# untitled.net
KiCad netlist of a schematic drawn in EAGLE
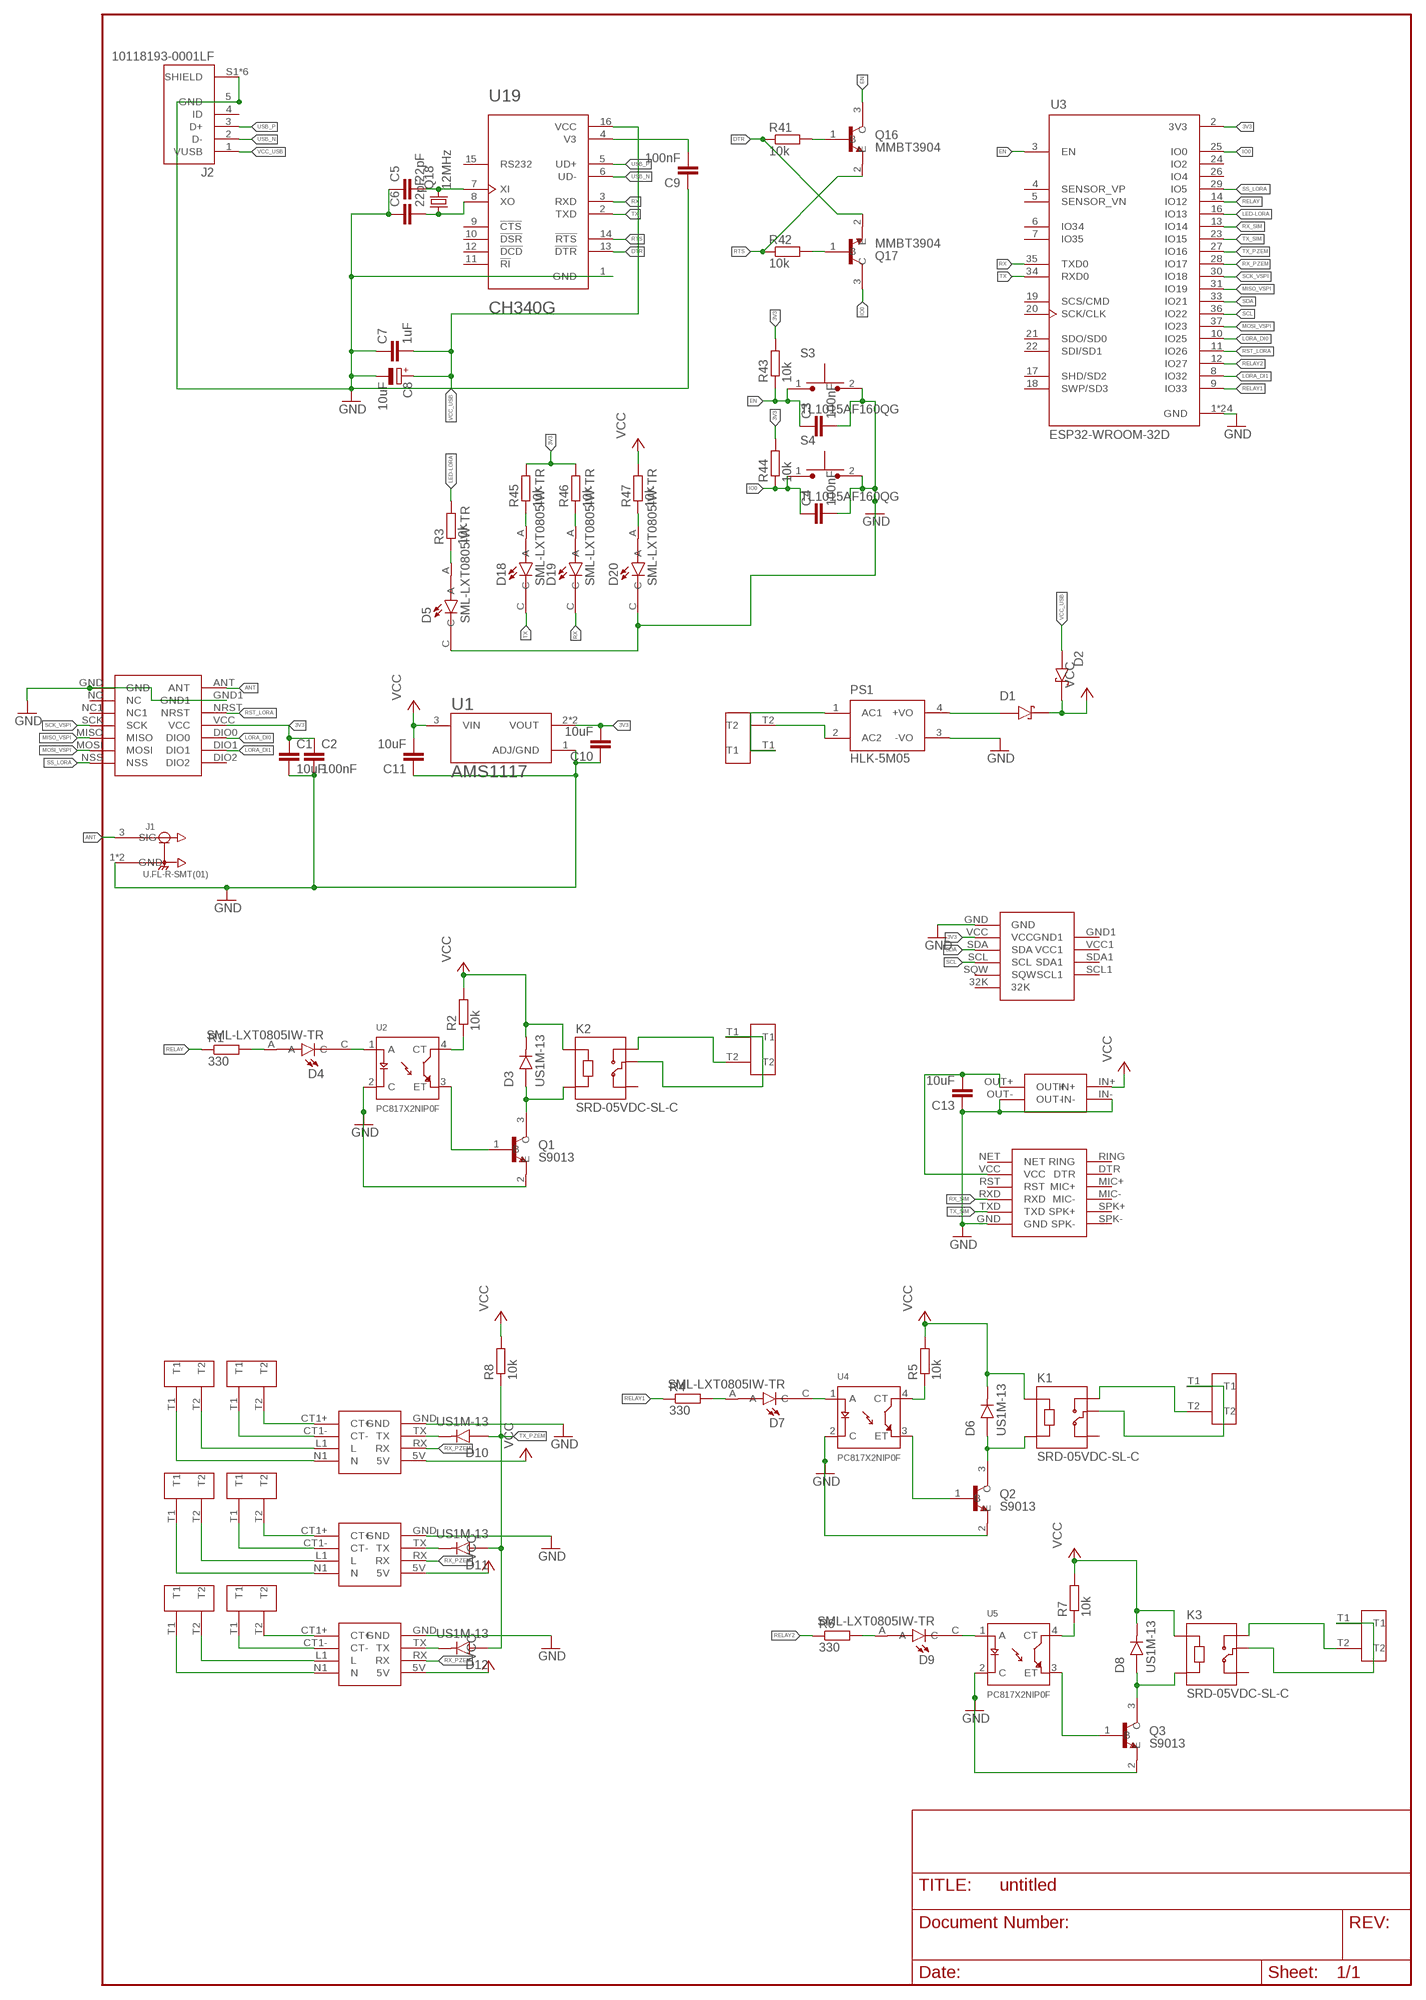
[diagram p0: schematic, sheet 1]

(export (version "E")
  (design (tool "Eeschema 10.0.6"))
  (components
    (comp (ref "C1")
      (value "10uF")
      (footprint "eagle-import:C0805K")
      (libsource (lib "eagle-import") (part "C-EUC0805K"))
    )
    (comp (ref "C2")
      (value "100nF")
      (footprint "eagle-import:C0805K")
      (libsource (lib "eagle-import") (part "C-EUC0805K"))
    )
    (comp (ref "C3")
      (value "100nF")
      (footprint "eagle-import:C0805K")
      (libsource (lib "eagle-import") (part "C-EUC0805K"))
    )
    (comp (ref "C4")
      (value "100nF")
      (footprint "eagle-import:C0805K")
      (libsource (lib "eagle-import") (part "C-EUC0805K"))
    )
    (comp (ref "C5")
      (value "22pF")
      (footprint "eagle-import:C0805K")
      (libsource (lib "eagle-import") (part "C-EUC0805K"))
    )
    (comp (ref "C6")
      (value "22pF")
      (footprint "eagle-import:C0805K")
      (libsource (lib "eagle-import") (part "C-EUC0805K"))
    )
    (comp (ref "C7")
      (value "1uF")
      (footprint "eagle-import:C0805K")
      (libsource (lib "eagle-import") (part "C-EUC0805K"))
    )
    (comp (ref "C8")
      (value "10uF")
      (footprint "eagle-import:153CLV-0505")
      (libsource (lib "eagle-import") (part "CPOL-EU153CLV-0505"))
    )
    (comp (ref "C9")
      (value "100nF")
      (footprint "eagle-import:C0805K")
      (libsource (lib "eagle-import") (part "C-EUC0805K"))
    )
    (comp (ref "C10")
      (value "10uF")
      (footprint "eagle-import:C0805K")
      (libsource (lib "eagle-import") (part "C-EUC0805K"))
    )
    (comp (ref "C11")
      (value "10uF")
      (footprint "eagle-import:C0805K")
      (libsource (lib "eagle-import") (part "C-EUC0805K"))
    )
    (comp (ref "C13")
      (value "10uF")
      (footprint "eagle-import:C0805K")
      (libsource (lib "eagle-import") (part "C-EUC0805K"))
    )
    (comp (ref "D1")
      (value "1N5819HW-7")
      (footprint "eagle-import:SOD3715X145N")
      (fields (field (name "MF") "Diodes Inc."))
      (libsource (lib "eagle-import") (part "1N5819HW-7"))
    )
    (comp (ref "D2")
      (value "1N5819HW-7")
      (footprint "eagle-import:SOD3715X145N")
      (fields (field (name "MF") "Diodes Inc."))
      (libsource (lib "eagle-import") (part "1N5819HW-7"))
    )
    (comp (ref "D3")
      (value "US1M-13")
      (footprint "eagle-import:DIOM5226X240N")
      (fields (field (name "MF") "Diodes Incorporated"))
      (libsource (lib "eagle-import") (part "US1M-13"))
    )
    (comp (ref "D4")
      (value "SML-LXT0805IW-TR")
      (footprint "eagle-import:LEDC2012X120N")
      (fields (field (name "MF") "Lumex Opto/Components"))
      (libsource (lib "eagle-import") (part "SML-LXT0805IW-TR"))
    )
    (comp (ref "D5")
      (value "SML-LXT0805IW-TR")
      (footprint "eagle-import:LEDC2012X120N")
      (fields (field (name "MF") "Lumex Opto/Components"))
      (libsource (lib "eagle-import") (part "SML-LXT0805IW-TR"))
    )
    (comp (ref "D6")
      (value "US1M-13")
      (footprint "eagle-import:DIOM5226X240N")
      (fields (field (name "MF") "Diodes Incorporated"))
      (libsource (lib "eagle-import") (part "US1M-13"))
    )
    (comp (ref "D7")
      (value "SML-LXT0805IW-TR")
      (footprint "eagle-import:LEDC2012X120N")
      (fields (field (name "MF") "Lumex Opto/Components"))
      (libsource (lib "eagle-import") (part "SML-LXT0805IW-TR"))
    )
    (comp (ref "D8")
      (value "US1M-13")
      (footprint "eagle-import:DIOM5226X240N")
      (fields (field (name "MF") "Diodes Incorporated"))
      (libsource (lib "eagle-import") (part "US1M-13"))
    )
    (comp (ref "D9")
      (value "SML-LXT0805IW-TR")
      (footprint "eagle-import:LEDC2012X120N")
      (fields (field (name "MF") "Lumex Opto/Components"))
      (libsource (lib "eagle-import") (part "SML-LXT0805IW-TR"))
    )
    (comp (ref "D10")
      (value "US1M-13")
      (footprint "eagle-import:DIOM5226X240N")
      (fields (field (name "MF") "Diodes Incorporated"))
      (libsource (lib "eagle-import") (part "US1M-13"))
    )
    (comp (ref "D11")
      (value "US1M-13")
      (footprint "eagle-import:DIOM5226X240N")
      (fields (field (name "MF") "Diodes Incorporated"))
      (libsource (lib "eagle-import") (part "US1M-13"))
    )
    (comp (ref "D12")
      (value "US1M-13")
      (footprint "eagle-import:DIOM5226X240N")
      (fields (field (name "MF") "Diodes Incorporated"))
      (libsource (lib "eagle-import") (part "US1M-13"))
    )
    (comp (ref "D18")
      (value "SML-LXT0805IW-TR")
      (footprint "eagle-import:LEDC2012X120N")
      (fields (field (name "MF") "Lumex Opto/Components"))
      (libsource (lib "eagle-import") (part "SML-LXT0805IW-TR"))
    )
    (comp (ref "D19")
      (value "SML-LXT0805IW-TR")
      (footprint "eagle-import:LEDC2012X120N")
      (fields (field (name "MF") "Lumex Opto/Components"))
      (libsource (lib "eagle-import") (part "SML-LXT0805IW-TR"))
    )
    (comp (ref "D20")
      (value "SML-LXT0805IW-TR")
      (footprint "eagle-import:LEDC2012X120N")
      (fields (field (name "MF") "Lumex Opto/Components"))
      (libsource (lib "eagle-import") (part "SML-LXT0805IW-TR"))
    )
    (comp (ref "J1")
      (value "U.FL-R-SMT(01)")
      (footprint "eagle-import:HRS_U.FL-R-SMT(01)")
      (fields (field (name "MF") "Hirose"))
      (libsource (lib "eagle-import") (part "U.FL-R-SMT(01)"))
    )
    (comp (ref "J2")
      (value "10118193-0001LF")
      (footprint "eagle-import:FCI_10118193-0001LF")
      (fields (field (name "MF") "FCI"))
      (libsource (lib "eagle-import") (part "10118193-0001LF"))
    )
    (comp (ref "K1")
      (value "SRD-05VDC-SL-C")
      (footprint "eagle-import:RELAY_SRD-05VDC-SL-C")
      (fields (field (name "MF") "Songle Relay"))
      (libsource (lib "eagle-import") (part "SRD-05VDC-SL-C"))
    )
    (comp (ref "K2")
      (value "SRD-05VDC-SL-C")
      (footprint "eagle-import:RELAY_SRD-05VDC-SL-C")
      (fields (field (name "MF") "Songle Relay"))
      (libsource (lib "eagle-import") (part "SRD-05VDC-SL-C"))
    )
    (comp (ref "K3")
      (value "SRD-05VDC-SL-C")
      (footprint "eagle-import:RELAY_SRD-05VDC-SL-C")
      (fields (field (name "MF") "Songle Relay"))
      (libsource (lib "eagle-import") (part "SRD-05VDC-SL-C"))
    )
    (comp (ref "LORA-NICERF-V1")
      (value "LORA-NICERF-V2")
      (footprint "eagle-import:LORA-NICERF-V2")
      (libsource (lib "eagle-import") (part "LORA-NICERF-V2"))
    )
    (comp (ref "MINI1")
      (value "MINI360")
      (footprint "eagle-import:MINI360")
      (libsource (lib "eagle-import") (part "MINI360"))
    )
    (comp (ref "PS1")
      (value "HLK-5M05")
      (footprint "eagle-import:CONV_HLK-5M05")
      (fields (field (name "MF") "Hi-link"))
      (libsource (lib "eagle-import") (part "HLK-5M05"))
    )
    (comp (ref "PZEM004T1")
      (value "PZEM004T")
      (footprint "eagle-import:PZEM004T")
      (libsource (lib "eagle-import") (part "PZEM004T"))
    )
    (comp (ref "PZEM004T2")
      (value "PZEM004T")
      (footprint "eagle-import:PZEM004T")
      (libsource (lib "eagle-import") (part "PZEM004T"))
    )
    (comp (ref "PZEM004T3")
      (value "PZEM004T")
      (footprint "eagle-import:PZEM004T")
      (libsource (lib "eagle-import") (part "PZEM004T"))
    )
    (comp (ref "Q1")
      (value "S9013")
      (footprint "eagle-import:SOT95P240X120-3N")
      (fields (field (name "MF") "JCET"))
      (libsource (lib "eagle-import") (part "S9013"))
    )
    (comp (ref "Q2")
      (value "S9013")
      (footprint "eagle-import:SOT95P240X120-3N")
      (fields (field (name "MF") "JCET"))
      (libsource (lib "eagle-import") (part "S9013"))
    )
    (comp (ref "Q3")
      (value "S9013")
      (footprint "eagle-import:SOT95P240X120-3N")
      (fields (field (name "MF") "JCET"))
      (libsource (lib "eagle-import") (part "S9013"))
    )
    (comp (ref "Q16")
      (value "MMBT3904")
      (footprint "eagle-import:SOT95P240X120-3N")
      (fields (field (name "MF") "ON Semiconductor"))
      (libsource (lib "eagle-import") (part "MMBT3904"))
    )
    (comp (ref "Q17")
      (value "MMBT3904")
      (footprint "eagle-import:SOT95P240X120-3N")
      (fields (field (name "MF") "ON Semiconductor"))
      (libsource (lib "eagle-import") (part "MMBT3904"))
    )
    (comp (ref "Q18")
      (value "12MHz")
      (footprint "eagle-import:SM49")
      (libsource (lib "eagle-import") (part "CRYSTALSM49"))
    )
    (comp (ref "R1")
      (value "330")
      (footprint "eagle-import:R0805")
      (libsource (lib "eagle-import") (part "R-EU_R0805"))
    )
    (comp (ref "R2")
      (value "10k")
      (footprint "eagle-import:R0805")
      (libsource (lib "eagle-import") (part "R-EU_R0805"))
    )
    (comp (ref "R3")
      (value "10k")
      (footprint "eagle-import:R0805")
      (libsource (lib "eagle-import") (part "R-EU_R0805"))
    )
    (comp (ref "R4")
      (value "330")
      (footprint "eagle-import:R0805")
      (libsource (lib "eagle-import") (part "R-EU_R0805"))
    )
    (comp (ref "R5")
      (value "10k")
      (footprint "eagle-import:R0805")
      (libsource (lib "eagle-import") (part "R-EU_R0805"))
    )
    (comp (ref "R6")
      (value "330")
      (footprint "eagle-import:R0805")
      (libsource (lib "eagle-import") (part "R-EU_R0805"))
    )
    (comp (ref "R7")
      (value "10k")
      (footprint "eagle-import:R0805")
      (libsource (lib "eagle-import") (part "R-EU_R0805"))
    )
    (comp (ref "R8")
      (value "10k")
      (footprint "eagle-import:R0805")
      (libsource (lib "eagle-import") (part "R-EU_R0805"))
    )
    (comp (ref "R41")
      (value "10k")
      (footprint "eagle-import:R0805")
      (libsource (lib "eagle-import") (part "R-EU_R0805"))
    )
    (comp (ref "R42")
      (value "10k")
      (footprint "eagle-import:R0805")
      (libsource (lib "eagle-import") (part "R-EU_R0805"))
    )
    (comp (ref "R43")
      (value "10k")
      (footprint "eagle-import:R0805")
      (libsource (lib "eagle-import") (part "R-EU_R0805"))
    )
    (comp (ref "R44")
      (value "10k")
      (footprint "eagle-import:R0805")
      (libsource (lib "eagle-import") (part "R-EU_R0805"))
    )
    (comp (ref "R45")
      (value "10k")
      (footprint "eagle-import:R0805")
      (libsource (lib "eagle-import") (part "R-EU_R0805"))
    )
    (comp (ref "R46")
      (value "10k")
      (footprint "eagle-import:R0805")
      (libsource (lib "eagle-import") (part "R-EU_R0805"))
    )
    (comp (ref "R47")
      (value "10k")
      (footprint "eagle-import:R0805")
      (libsource (lib "eagle-import") (part "R-EU_R0805"))
    )
    (comp (ref "RTC1")
      (value "RTC3231")
      (footprint "eagle-import:RTC3231")
      (libsource (lib "eagle-import") (part "RTC3231"))
    )
    (comp (ref "S3")
      (value "TL1015AF160QG")
      (footprint "eagle-import:SW_TL1015AF160QG")
      (fields (field (name "MF") "E-Switch"))
      (libsource (lib "eagle-import") (part "TL1015AF160QG"))
    )
    (comp (ref "S4")
      (value "TL1015AF160QG")
      (footprint "eagle-import:SW_TL1015AF160QG")
      (fields (field (name "MF") "E-Switch"))
      (libsource (lib "eagle-import") (part "TL1015AF160QG"))
    )
    (comp (ref "SIM800L1")
      (value "SIM800L")
      (footprint "eagle-import:SIM800L")
      (libsource (lib "eagle-import") (part "SIM800L"))
    )
    (comp (ref "TB7.1")
      (value "TB7.62")
      (footprint "eagle-import:TB7.62")
      (libsource (lib "eagle-import") (part "TB7.62"))
    )
    (comp (ref "TB7.2")
      (value "TB7.62")
      (footprint "eagle-import:TB7.62")
      (libsource (lib "eagle-import") (part "TB7.62"))
    )
    (comp (ref "TB7.3")
      (value "TB7.62")
      (footprint "eagle-import:TB7.62")
      (libsource (lib "eagle-import") (part "TB7.62"))
    )
    (comp (ref "TB7.4")
      (value "TB7.62")
      (footprint "eagle-import:TB7.62")
      (libsource (lib "eagle-import") (part "TB7.62"))
    )
    (comp (ref "TB7.5")
      (value "TB7.62")
      (footprint "eagle-import:TB7.62")
      (libsource (lib "eagle-import") (part "TB7.62"))
    )
    (comp (ref "TB7.6")
      (value "TB7.62")
      (footprint "eagle-import:TB7.62")
      (libsource (lib "eagle-import") (part "TB7.62"))
    )
    (comp (ref "TB7.7")
      (value "TB7.62")
      (footprint "eagle-import:TB7.62")
      (libsource (lib "eagle-import") (part "TB7.62"))
    )
    (comp (ref "TB7.8")
      (value "TB7.62")
      (footprint "eagle-import:TB7.62")
      (libsource (lib "eagle-import") (part "TB7.62"))
    )
    (comp (ref "TB7.9")
      (value "TB7.62")
      (footprint "eagle-import:TB7.62")
      (libsource (lib "eagle-import") (part "TB7.62"))
    )
    (comp (ref "TB7.10")
      (value "TB7.62")
      (footprint "eagle-import:TB7.62")
      (libsource (lib "eagle-import") (part "TB7.62"))
    )
    (comp (ref "U1")
      (value "AMS1117")
      (footprint "eagle-import:SOT229P700X180-4N")
      (fields (field (name "MF") "Advanced Monolithic Systems"))
      (libsource (lib "eagle-import") (part "AMS1117"))
    )
    (comp (ref "U2")
      (value "PC817X2NIP0F")
      (footprint "eagle-import:SOT254P975X400-4N")
      (fields (field (name "MF") "Sharp Microelectronics"))
      (libsource (lib "eagle-import") (part "PC817X2NIP0F"))
    )
    (comp (ref "U3")
      (value "ESP32-WROOM-32D")
      (footprint "eagle-import:MODULE_ESP32-WROOM-32D")
      (fields (field (name "MF") "Espressif Systems"))
      (libsource (lib "eagle-import") (part "ESP32-WROOM-32D"))
    )
    (comp (ref "U4")
      (value "PC817X2NIP0F")
      (footprint "eagle-import:SOT254P975X400-4N")
      (fields (field (name "MF") "Sharp Microelectronics"))
      (libsource (lib "eagle-import") (part "PC817X2NIP0F"))
    )
    (comp (ref "U5")
      (value "PC817X2NIP0F")
      (footprint "eagle-import:SOT254P975X400-4N")
      (fields (field (name "MF") "Sharp Microelectronics"))
      (libsource (lib "eagle-import") (part "PC817X2NIP0F"))
    )
    (comp (ref "U19")
      (value "CH340G")
      (footprint "eagle-import:SOIC127P600X180-16N")
      (fields (field (name "MF") "WCH") (field (name "MP") "Ch340G"))
      (libsource (lib "eagle-import") (part "CH340G"))
    )
  )
  (nets
    (net (code "1") (name "3V3") (class "Default")
      (node (ref "C1") (pin "1") (pinfunction "1_1") (pintype "passive"))
      (node (ref "C10") (pin "2") (pinfunction "2_2") (pintype "passive"))
      (node (ref "C2") (pin "1") (pinfunction "1_1") (pintype "passive"))
      (node (ref "LORA-NICERF-V1") (pin "VCC") (pinfunction "VCC_VCC") (pintype "bidirectional"))
      (node (ref "R43") (pin "2") (pinfunction "2_2") (pintype "passive"))
      (node (ref "R44") (pin "2") (pinfunction "2_2") (pintype "passive"))
      (node (ref "R45") (pin "2") (pinfunction "2_2") (pintype "passive"))
      (node (ref "R46") (pin "2") (pinfunction "2_2") (pintype "passive"))
      (node (ref "RTC1") (pin "VCC") (pinfunction "VCC_VCC") (pintype "bidirectional"))
      (node (ref "U1") (pin "2") (pinfunction "VOUT_2") (pintype "output"))
      (node (ref "U1") (pin "4") (pinfunction "VOUT_4") (pintype "output"))
      (node (ref "U3") (pin "2") (pinfunction "3V3_2") (pintype "power_in"))
    )
    (net (code "2") (name "ANT") (class "Default")
      (node (ref "J1") (pin "3") (pinfunction "SIG_3") (pintype "passive"))
      (node (ref "LORA-NICERF-V1") (pin "ANT") (pinfunction "ANT_ANT") (pintype "bidirectional"))
    )
    (net (code "3") (name "DTR") (class "Default")
      (node (ref "Q17") (pin "2") (pinfunction "E_2") (pintype "passive"))
      (node (ref "R41") (pin "1") (pinfunction "1_1") (pintype "passive"))
      (node (ref "U19") (pin "13") (pinfunction "~{DTR}_13") (pintype "output"))
    )
    (net (code "4") (name "EN") (class "Default")
      (node (ref "C3") (pin "1") (pinfunction "1_1") (pintype "passive"))
      (node (ref "Q16") (pin "3") (pinfunction "C_3") (pintype "passive"))
      (node (ref "R43") (pin "1") (pinfunction "1_1") (pintype "passive"))
      (node (ref "S3") (pin "1") (pinfunction "1_1") (pintype "passive"))
      (node (ref "U3") (pin "3") (pinfunction "EN_3") (pintype "input"))
    )
    (net (code "5") (name "GND") (class "Default")
      (node (ref "C1") (pin "2") (pinfunction "2_2") (pintype "passive"))
      (node (ref "C10") (pin "1") (pinfunction "1_1") (pintype "passive"))
      (node (ref "C11") (pin "1") (pinfunction "1_1") (pintype "passive"))
      (node (ref "C13") (pin "1") (pinfunction "1_1") (pintype "passive"))
      (node (ref "C2") (pin "2") (pinfunction "2_2") (pintype "passive"))
      (node (ref "C3") (pin "2") (pinfunction "2_2") (pintype "passive"))
      (node (ref "C4") (pin "2") (pinfunction "2_2") (pintype "passive"))
      (node (ref "C5") (pin "1") (pinfunction "1_1") (pintype "passive"))
      (node (ref "C6") (pin "1") (pinfunction "1_1") (pintype "passive"))
      (node (ref "C7") (pin "1") (pinfunction "1_1") (pintype "passive"))
      (node (ref "C8") (pin "-") (pinfunction "-_-") (pintype "passive"))
      (node (ref "C9") (pin "1") (pinfunction "1_1") (pintype "passive"))
      (node (ref "D20") (pin "C") (pinfunction "C_C") (pintype "passive"))
      (node (ref "D5") (pin "C") (pinfunction "C_C") (pintype "passive"))
      (node (ref "J1") (pin "1") (pinfunction "GND_1") (pintype "passive"))
      (node (ref "J1") (pin "2") (pinfunction "GND_2") (pintype "passive"))
      (node (ref "J2") (pin "5") (pinfunction "GND_5") (pintype "passive"))
      (node (ref "J2") (pin "S1") (pinfunction "SHIELD_S1") (pintype "passive"))
      (node (ref "J2") (pin "S2") (pinfunction "SHIELD_S2") (pintype "passive"))
      (node (ref "J2") (pin "S3") (pinfunction "SHIELD_S3") (pintype "passive"))
      (node (ref "J2") (pin "S4") (pinfunction "SHIELD_S4") (pintype "passive"))
      (node (ref "J2") (pin "S5") (pinfunction "SHIELD_S5") (pintype "passive"))
      (node (ref "J2") (pin "S6") (pinfunction "SHIELD_S6") (pintype "passive"))
      (node (ref "LORA-NICERF-V1") (pin "GND") (pinfunction "GND_GND") (pintype "bidirectional"))
      (node (ref "LORA-NICERF-V1") (pin "GND1") (pinfunction "GND1_GND1") (pintype "bidirectional"))
      (node (ref "MINI1") (pin "IN-") (pinfunction "IN-_IN-") (pintype "bidirectional"))
      (node (ref "MINI1") (pin "OUT-") (pinfunction "OUT-_OUT-") (pintype "bidirectional"))
      (node (ref "PS1") (pin "3") (pinfunction "-VO_3") (pintype "output"))
      (node (ref "PZEM004T1") (pin "GND") (pinfunction "GND_GND") (pintype "bidirectional"))
      (node (ref "PZEM004T2") (pin "GND") (pinfunction "GND_GND") (pintype "bidirectional"))
      (node (ref "PZEM004T3") (pin "GND") (pinfunction "GND_GND") (pintype "bidirectional"))
      (node (ref "Q1") (pin "2") (pinfunction "E_2") (pintype "passive"))
      (node (ref "Q2") (pin "2") (pinfunction "E_2") (pintype "passive"))
      (node (ref "Q3") (pin "2") (pinfunction "E_2") (pintype "passive"))
      (node (ref "RTC1") (pin "GND") (pinfunction "GND_GND") (pintype "bidirectional"))
      (node (ref "S3") (pin "2") (pinfunction "2_2") (pintype "passive"))
      (node (ref "S4") (pin "2") (pinfunction "2_2") (pintype "passive"))
      (node (ref "SIM800L1") (pin "GND") (pinfunction "GND_GND") (pintype "bidirectional"))
      (node (ref "U1") (pin "1") (pinfunction "ADJ/GND_1") (pintype "power_in"))
      (node (ref "U19") (pin "1") (pinfunction "GND_1") (pintype "power_in"))
      (node (ref "U2") (pin "2") (pinfunction "C_2") (pintype "passive"))
      (node (ref "U3") (pin "1") (pinfunction "GND_1") (pintype "power_in"))
      (node (ref "U3") (pin "15") (pinfunction "GND_15") (pintype "power_in"))
      (node (ref "U3") (pin "38") (pinfunction "GND_38") (pintype "power_in"))
      (node (ref "U3") (pin "39_1") (pinfunction "GND_39_1") (pintype "power_in"))
      (node (ref "U3") (pin "39_10") (pinfunction "GND_39_10") (pintype "power_in"))
      (node (ref "U3") (pin "39_11") (pinfunction "GND_39_11") (pintype "power_in"))
      (node (ref "U3") (pin "39_12") (pinfunction "GND_39_12") (pintype "power_in"))
      (node (ref "U3") (pin "39_13") (pinfunction "GND_39_13") (pintype "power_in"))
      (node (ref "U3") (pin "39_14") (pinfunction "GND_39_14") (pintype "power_in"))
      (node (ref "U3") (pin "39_15") (pinfunction "GND_39_15") (pintype "power_in"))
      (node (ref "U3") (pin "39_16") (pinfunction "GND_39_16") (pintype "power_in"))
      (node (ref "U3") (pin "39_17") (pinfunction "GND_39_17") (pintype "power_in"))
      (node (ref "U3") (pin "39_18") (pinfunction "GND_39_18") (pintype "power_in"))
      (node (ref "U3") (pin "39_19") (pinfunction "GND_39_19") (pintype "power_in"))
      (node (ref "U3") (pin "39_2") (pinfunction "GND_39_2") (pintype "power_in"))
      (node (ref "U3") (pin "39_20") (pinfunction "GND_39_20") (pintype "power_in"))
      (node (ref "U3") (pin "39_21") (pinfunction "GND_39_21") (pintype "power_in"))
      (node (ref "U3") (pin "39_3") (pinfunction "GND_39_3") (pintype "power_in"))
      (node (ref "U3") (pin "39_4") (pinfunction "GND_39_4") (pintype "power_in"))
      (node (ref "U3") (pin "39_5") (pinfunction "GND_39_5") (pintype "power_in"))
      (node (ref "U3") (pin "39_6") (pinfunction "GND_39_6") (pintype "power_in"))
      (node (ref "U3") (pin "39_7") (pinfunction "GND_39_7") (pintype "power_in"))
      (node (ref "U3") (pin "39_8") (pinfunction "GND_39_8") (pintype "power_in"))
      (node (ref "U3") (pin "39_9") (pinfunction "GND_39_9") (pintype "power_in"))
      (node (ref "U4") (pin "2") (pinfunction "C_2") (pintype "passive"))
      (node (ref "U5") (pin "2") (pinfunction "C_2") (pintype "passive"))
    )
    (net (code "6") (name "IO0") (class "Default")
      (node (ref "C4") (pin "1") (pinfunction "1_1") (pintype "passive"))
      (node (ref "Q17") (pin "3") (pinfunction "C_3") (pintype "passive"))
      (node (ref "R44") (pin "1") (pinfunction "1_1") (pintype "passive"))
      (node (ref "S4") (pin "1") (pinfunction "1_1") (pintype "passive"))
      (node (ref "U3") (pin "25") (pinfunction "IO0_25") (pintype "bidirectional"))
    )
    (net (code "7") (name "LED-LORA") (class "Default")
      (node (ref "R3") (pin "2") (pinfunction "2_2") (pintype "passive"))
      (node (ref "U3") (pin "16") (pinfunction "IO13_16") (pintype "bidirectional"))
    )
    (net (code "8") (name "LORA_DI0") (class "Default")
      (node (ref "LORA-NICERF-V1") (pin "DIO0") (pinfunction "DIO0_DIO0") (pintype "bidirectional"))
      (node (ref "U3") (pin "10") (pinfunction "IO25_10") (pintype "bidirectional"))
    )
    (net (code "9") (name "LORA_DI1") (class "Default")
      (node (ref "LORA-NICERF-V1") (pin "DIO1") (pinfunction "DIO1_DIO1") (pintype "bidirectional"))
      (node (ref "U3") (pin "8") (pinfunction "IO32_8") (pintype "bidirectional"))
    )
    (net (code "10") (name "MISO_VSPI") (class "Default")
      (node (ref "LORA-NICERF-V1") (pin "MISO") (pinfunction "MISO_MISO") (pintype "bidirectional"))
      (node (ref "U3") (pin "31") (pinfunction "IO19_31") (pintype "bidirectional"))
    )
    (net (code "11") (name "MOSI_VSPI") (class "Default")
      (node (ref "LORA-NICERF-V1") (pin "MOSI") (pinfunction "MOSI_MOSI") (pintype "bidirectional"))
      (node (ref "U3") (pin "37") (pinfunction "IO23_37") (pintype "bidirectional"))
    )
    (net (code "12") (name "Net-(C13-Pad2)") (class "Default")
      (node (ref "C13") (pin "2") (pinfunction "2_2") (pintype "passive"))
      (node (ref "MINI1") (pin "OUT+") (pinfunction "OUT+_OUT+") (pintype "bidirectional"))
      (node (ref "SIM800L1") (pin "VCC") (pinfunction "VCC_VCC") (pintype "bidirectional"))
    )
    (net (code "13") (name "Net-(D4-PadA)") (class "Default")
      (node (ref "D4") (pin "A") (pinfunction "A_A") (pintype "passive"))
      (node (ref "R1") (pin "2") (pinfunction "2_2") (pintype "passive"))
    )
    (net (code "14") (name "Net-(D5-PadA)") (class "Default")
      (node (ref "D5") (pin "A") (pinfunction "A_A") (pintype "passive"))
      (node (ref "R3") (pin "1") (pinfunction "1_1") (pintype "passive"))
    )
    (net (code "15") (name "Net-(D7-PadA)") (class "Default")
      (node (ref "D7") (pin "A") (pinfunction "A_A") (pintype "passive"))
      (node (ref "R4") (pin "2") (pinfunction "2_2") (pintype "passive"))
    )
    (net (code "16") (name "Net-(D9-PadA)") (class "Default")
      (node (ref "D9") (pin "A") (pinfunction "A_A") (pintype "passive"))
      (node (ref "R6") (pin "2") (pinfunction "2_2") (pintype "passive"))
    )
    (net (code "17") (name "Net-(D10-K)") (class "Default")
      (node (ref "D10") (pin "C") (pinfunction "K_C") (pintype "passive"))
      (node (ref "PZEM004T1") (pin "TX") (pinfunction "TX_TX") (pintype "bidirectional"))
    )
    (net (code "18") (name "Net-(D11-K)") (class "Default")
      (node (ref "D11") (pin "C") (pinfunction "K_C") (pintype "passive"))
      (node (ref "PZEM004T2") (pin "TX") (pinfunction "TX_TX") (pintype "bidirectional"))
    )
    (net (code "19") (name "Net-(D12-K)") (class "Default")
      (node (ref "D12") (pin "C") (pinfunction "K_C") (pintype "passive"))
      (node (ref "PZEM004T3") (pin "TX") (pinfunction "TX_TX") (pintype "bidirectional"))
    )
    (net (code "20") (name "Net-(D18-PadA)") (class "Default")
      (node (ref "D18") (pin "A") (pinfunction "A_A") (pintype "passive"))
      (node (ref "R45") (pin "1") (pinfunction "1_1") (pintype "passive"))
    )
    (net (code "21") (name "Net-(D19-PadA)") (class "Default")
      (node (ref "D19") (pin "A") (pinfunction "A_A") (pintype "passive"))
      (node (ref "R46") (pin "1") (pinfunction "1_1") (pintype "passive"))
    )
    (net (code "22") (name "Net-(D20-PadA)") (class "Default")
      (node (ref "D20") (pin "A") (pinfunction "A_A") (pintype "passive"))
      (node (ref "R47") (pin "1") (pinfunction "1_1") (pintype "passive"))
    )
    (net (code "23") (name "Net-(K1-PadCOM)") (class "Default")
      (node (ref "K1") (pin "COM") (pinfunction "COM_COM") (pintype "passive"))
      (node (ref "TB7.9") (pin "T1") (pinfunction "T1_T1") (pintype "bidirectional"))
    )
    (net (code "24") (name "Net-(K1-PadNO)") (class "Default")
      (node (ref "K1") (pin "NO") (pinfunction "NO_NO") (pintype "passive"))
      (node (ref "TB7.9") (pin "T2") (pinfunction "T2_T2") (pintype "bidirectional"))
    )
    (net (code "25") (name "Net-(K2-PadCOM)") (class "Default")
      (node (ref "K2") (pin "COM") (pinfunction "COM_COM") (pintype "passive"))
      (node (ref "TB7.2") (pin "T1") (pinfunction "T1_T1") (pintype "bidirectional"))
    )
    (net (code "26") (name "Net-(K2-PadNO)") (class "Default")
      (node (ref "K2") (pin "NO") (pinfunction "NO_NO") (pintype "passive"))
      (node (ref "TB7.2") (pin "T2") (pinfunction "T2_T2") (pintype "bidirectional"))
    )
    (net (code "27") (name "Net-(K3-PadCOM)") (class "Default")
      (node (ref "K3") (pin "COM") (pinfunction "COM_COM") (pintype "passive"))
      (node (ref "TB7.10") (pin "T1") (pinfunction "T1_T1") (pintype "bidirectional"))
    )
    (net (code "28") (name "Net-(K3-PadNO)") (class "Default")
      (node (ref "K3") (pin "NO") (pinfunction "NO_NO") (pintype "passive"))
      (node (ref "TB7.10") (pin "T2") (pinfunction "T2_T2") (pintype "bidirectional"))
    )
    (net (code "29") (name "Net-(PS1-+VO)") (class "Default")
      (node (ref "D1") (pin "A") (pinfunction "A_A") (pintype "passive"))
      (node (ref "PS1") (pin "4") (pinfunction "+VO_4") (pintype "output"))
    )
    (net (code "30") (name "Net-(PS1-AC1)") (class "Default")
      (node (ref "PS1") (pin "1") (pinfunction "AC1_1") (pintype "input"))
      (node (ref "TB7.1") (pin "T1") (pinfunction "T1_T1") (pintype "bidirectional"))
    )
    (net (code "31") (name "Net-(PS1-AC2)") (class "Default")
      (node (ref "PS1") (pin "2") (pinfunction "AC2_2") (pintype "input"))
      (node (ref "TB7.1") (pin "T2") (pinfunction "T2_T2") (pintype "bidirectional"))
    )
    (net (code "32") (name "Net-(PZEM004T1-CT+)") (class "Default")
      (node (ref "PZEM004T1") (pin "CT1+") (pinfunction "CT+_CT1+") (pintype "bidirectional"))
      (node (ref "TB7.3") (pin "T2") (pinfunction "T2_T2") (pintype "bidirectional"))
    )
    (net (code "33") (name "Net-(PZEM004T1-CT-)") (class "Default")
      (node (ref "PZEM004T1") (pin "CT1-") (pinfunction "CT-_CT1-") (pintype "bidirectional"))
      (node (ref "TB7.3") (pin "T1") (pinfunction "T1_T1") (pintype "bidirectional"))
    )
    (net (code "34") (name "Net-(PZEM004T1-L)") (class "Default")
      (node (ref "PZEM004T1") (pin "L1") (pinfunction "L_L1") (pintype "bidirectional"))
      (node (ref "TB7.4") (pin "T2") (pinfunction "T2_T2") (pintype "bidirectional"))
    )
    (net (code "35") (name "Net-(PZEM004T1-N)") (class "Default")
      (node (ref "PZEM004T1") (pin "N1") (pinfunction "N_N1") (pintype "bidirectional"))
      (node (ref "TB7.4") (pin "T1") (pinfunction "T1_T1") (pintype "bidirectional"))
    )
    (net (code "36") (name "Net-(PZEM004T2-CT+)") (class "Default")
      (node (ref "PZEM004T2") (pin "CT1+") (pinfunction "CT+_CT1+") (pintype "bidirectional"))
      (node (ref "TB7.5") (pin "T2") (pinfunction "T2_T2") (pintype "bidirectional"))
    )
    (net (code "37") (name "Net-(PZEM004T2-CT-)") (class "Default")
      (node (ref "PZEM004T2") (pin "CT1-") (pinfunction "CT-_CT1-") (pintype "bidirectional"))
      (node (ref "TB7.5") (pin "T1") (pinfunction "T1_T1") (pintype "bidirectional"))
    )
    (net (code "38") (name "Net-(PZEM004T2-L)") (class "Default")
      (node (ref "PZEM004T2") (pin "L1") (pinfunction "L_L1") (pintype "bidirectional"))
      (node (ref "TB7.6") (pin "T2") (pinfunction "T2_T2") (pintype "bidirectional"))
    )
    (net (code "39") (name "Net-(PZEM004T2-N)") (class "Default")
      (node (ref "PZEM004T2") (pin "N1") (pinfunction "N_N1") (pintype "bidirectional"))
      (node (ref "TB7.6") (pin "T1") (pinfunction "T1_T1") (pintype "bidirectional"))
    )
    (net (code "40") (name "Net-(PZEM004T3-CT+)") (class "Default")
      (node (ref "PZEM004T3") (pin "CT1+") (pinfunction "CT+_CT1+") (pintype "bidirectional"))
      (node (ref "TB7.7") (pin "T2") (pinfunction "T2_T2") (pintype "bidirectional"))
    )
    (net (code "41") (name "Net-(PZEM004T3-CT-)") (class "Default")
      (node (ref "PZEM004T3") (pin "CT1-") (pinfunction "CT-_CT1-") (pintype "bidirectional"))
      (node (ref "TB7.7") (pin "T1") (pinfunction "T1_T1") (pintype "bidirectional"))
    )
    (net (code "42") (name "Net-(PZEM004T3-L)") (class "Default")
      (node (ref "PZEM004T3") (pin "L1") (pinfunction "L_L1") (pintype "bidirectional"))
      (node (ref "TB7.8") (pin "T2") (pinfunction "T2_T2") (pintype "bidirectional"))
    )
    (net (code "43") (name "Net-(PZEM004T3-N)") (class "Default")
      (node (ref "PZEM004T3") (pin "N1") (pinfunction "N_N1") (pintype "bidirectional"))
      (node (ref "TB7.8") (pin "T1") (pinfunction "T1_T1") (pintype "bidirectional"))
    )
    (net (code "44") (name "Net-(Q1-B)") (class "Default")
      (node (ref "Q1") (pin "1") (pinfunction "B_1") (pintype "passive"))
      (node (ref "U2") (pin "3") (pinfunction "ET_3") (pintype "passive"))
    )
    (net (code "45") (name "Net-(Q1-C)") (class "Default")
      (node (ref "D3") (pin "A") (pinfunction "A_A") (pintype "passive"))
      (node (ref "K2") (pin "A2") (pinfunction "A2_A2") (pintype "passive"))
      (node (ref "Q1") (pin "3") (pinfunction "C_3") (pintype "passive"))
    )
    (net (code "46") (name "Net-(Q2-B)") (class "Default")
      (node (ref "Q2") (pin "1") (pinfunction "B_1") (pintype "passive"))
      (node (ref "U4") (pin "3") (pinfunction "ET_3") (pintype "passive"))
    )
    (net (code "47") (name "Net-(Q2-C)") (class "Default")
      (node (ref "D6") (pin "A") (pinfunction "A_A") (pintype "passive"))
      (node (ref "K1") (pin "A2") (pinfunction "A2_A2") (pintype "passive"))
      (node (ref "Q2") (pin "3") (pinfunction "C_3") (pintype "passive"))
    )
    (net (code "48") (name "Net-(Q3-B)") (class "Default")
      (node (ref "Q3") (pin "1") (pinfunction "B_1") (pintype "passive"))
      (node (ref "U5") (pin "3") (pinfunction "ET_3") (pintype "passive"))
    )
    (net (code "49") (name "Net-(Q3-C)") (class "Default")
      (node (ref "D8") (pin "A") (pinfunction "A_A") (pintype "passive"))
      (node (ref "K3") (pin "A2") (pinfunction "A2_A2") (pintype "passive"))
      (node (ref "Q3") (pin "3") (pinfunction "C_3") (pintype "passive"))
    )
    (net (code "50") (name "Net-(Q16-B)") (class "Default")
      (node (ref "Q16") (pin "1") (pinfunction "B_1") (pintype "passive"))
      (node (ref "R41") (pin "2") (pinfunction "2_2") (pintype "passive"))
    )
    (net (code "51") (name "Net-(Q17-B)") (class "Default")
      (node (ref "Q17") (pin "1") (pinfunction "B_1") (pintype "passive"))
      (node (ref "R42") (pin "2") (pinfunction "2_2") (pintype "passive"))
    )
    (net (code "52") (name "Net-(U2-A)") (class "Default")
      (node (ref "D4") (pin "C") (pinfunction "C_C") (pintype "passive"))
      (node (ref "U2") (pin "1") (pinfunction "A_1") (pintype "passive"))
    )
    (net (code "53") (name "Net-(U2-CT)") (class "Default")
      (node (ref "R2") (pin "1") (pinfunction "1_1") (pintype "passive"))
      (node (ref "U2") (pin "4") (pinfunction "CT_4") (pintype "passive"))
    )
    (net (code "54") (name "Net-(U4-A)") (class "Default")
      (node (ref "D7") (pin "C") (pinfunction "C_C") (pintype "passive"))
      (node (ref "U4") (pin "1") (pinfunction "A_1") (pintype "passive"))
    )
    (net (code "55") (name "Net-(U4-CT)") (class "Default")
      (node (ref "R5") (pin "1") (pinfunction "1_1") (pintype "passive"))
      (node (ref "U4") (pin "4") (pinfunction "CT_4") (pintype "passive"))
    )
    (net (code "56") (name "Net-(U5-A)") (class "Default")
      (node (ref "D9") (pin "C") (pinfunction "C_C") (pintype "passive"))
      (node (ref "U5") (pin "1") (pinfunction "A_1") (pintype "passive"))
    )
    (net (code "57") (name "Net-(U5-CT)") (class "Default")
      (node (ref "R7") (pin "1") (pinfunction "1_1") (pintype "passive"))
      (node (ref "U5") (pin "4") (pinfunction "CT_4") (pintype "passive"))
    )
    (net (code "58") (name "Net-(U19-V3)") (class "Default")
      (node (ref "C9") (pin "2") (pinfunction "2_2") (pintype "passive"))
      (node (ref "U19") (pin "4") (pinfunction "V3_4") (pintype "power_in"))
    )
    (net (code "59") (name "Net-(U19-XI)") (class "Default")
      (node (ref "C5") (pin "2") (pinfunction "2_2") (pintype "passive"))
      (node (ref "Q18") (pin "2") (pinfunction "2_2") (pintype "passive"))
      (node (ref "U19") (pin "7") (pinfunction "XI_7") (pintype "input"))
    )
    (net (code "60") (name "Net-(U19-XO)") (class "Default")
      (node (ref "C6") (pin "2") (pinfunction "2_2") (pintype "passive"))
      (node (ref "Q18") (pin "1") (pinfunction "1_1") (pintype "passive"))
      (node (ref "U19") (pin "8") (pinfunction "XO_8") (pintype "output"))
    )
    (net (code "61") (name "RELAY") (class "Default")
      (node (ref "R1") (pin "1") (pinfunction "1_1") (pintype "passive"))
      (node (ref "U3") (pin "14") (pinfunction "IO12_14") (pintype "bidirectional"))
    )
    (net (code "62") (name "RELAY1") (class "Default")
      (node (ref "R4") (pin "1") (pinfunction "1_1") (pintype "passive"))
      (node (ref "U3") (pin "9") (pinfunction "IO33_9") (pintype "bidirectional"))
    )
    (net (code "63") (name "RELAY2") (class "Default")
      (node (ref "R6") (pin "1") (pinfunction "1_1") (pintype "passive"))
      (node (ref "U3") (pin "12") (pinfunction "IO27_12") (pintype "bidirectional"))
    )
    (net (code "64") (name "RST_LORA") (class "Default")
      (node (ref "LORA-NICERF-V1") (pin "NRST") (pinfunction "NRST_NRST") (pintype "bidirectional"))
      (node (ref "U3") (pin "11") (pinfunction "IO26_11") (pintype "bidirectional"))
    )
    (net (code "65") (name "RTS") (class "Default")
      (node (ref "Q16") (pin "2") (pinfunction "E_2") (pintype "passive"))
      (node (ref "R42") (pin "1") (pinfunction "1_1") (pintype "passive"))
      (node (ref "U19") (pin "14") (pinfunction "~{RTS}_14") (pintype "output"))
    )
    (net (code "66") (name "RX") (class "Default")
      (node (ref "D19") (pin "C") (pinfunction "C_C") (pintype "passive"))
      (node (ref "U19") (pin "3") (pinfunction "RXD_3") (pintype "input"))
      (node (ref "U3") (pin "35") (pinfunction "TXD0_35") (pintype "bidirectional"))
    )
    (net (code "67") (name "RX_PZEM") (class "Default")
      (node (ref "PZEM004T1") (pin "RX") (pinfunction "RX_RX") (pintype "bidirectional"))
      (node (ref "PZEM004T2") (pin "RX") (pinfunction "RX_RX") (pintype "bidirectional"))
      (node (ref "PZEM004T3") (pin "RX") (pinfunction "RX_RX") (pintype "bidirectional"))
      (node (ref "U3") (pin "28") (pinfunction "IO17_28") (pintype "bidirectional"))
    )
    (net (code "68") (name "RX_SIM") (class "Default")
      (node (ref "SIM800L1") (pin "RXD") (pinfunction "RXD_RXD") (pintype "bidirectional"))
      (node (ref "U3") (pin "13") (pinfunction "IO14_13") (pintype "bidirectional"))
    )
    (net (code "69") (name "SCK_VSPI") (class "Default")
      (node (ref "LORA-NICERF-V1") (pin "SCK") (pinfunction "SCK_SCK") (pintype "bidirectional"))
      (node (ref "U3") (pin "30") (pinfunction "IO18_30") (pintype "bidirectional"))
    )
    (net (code "70") (name "SCL") (class "Default")
      (node (ref "RTC1") (pin "SCL") (pinfunction "SCL_SCL") (pintype "bidirectional"))
      (node (ref "U3") (pin "36") (pinfunction "IO22_36") (pintype "bidirectional"))
    )
    (net (code "71") (name "SDA") (class "Default")
      (node (ref "RTC1") (pin "SDA") (pinfunction "SDA_SDA") (pintype "bidirectional"))
      (node (ref "U3") (pin "33") (pinfunction "IO21_33") (pintype "bidirectional"))
    )
    (net (code "72") (name "SS_LORA") (class "Default")
      (node (ref "LORA-NICERF-V1") (pin "NSS") (pinfunction "NSS_NSS") (pintype "bidirectional"))
      (node (ref "U3") (pin "29") (pinfunction "IO5_29") (pintype "bidirectional"))
    )
    (net (code "73") (name "TX") (class "Default")
      (node (ref "D18") (pin "C") (pinfunction "C_C") (pintype "passive"))
      (node (ref "U19") (pin "2") (pinfunction "TXD_2") (pintype "output"))
      (node (ref "U3") (pin "34") (pinfunction "RXD0_34") (pintype "bidirectional"))
    )
    (net (code "74") (name "TX_PZEM") (class "Default")
      (node (ref "D10") (pin "A") (pinfunction "A_A") (pintype "passive"))
      (node (ref "D11") (pin "A") (pinfunction "A_A") (pintype "passive"))
      (node (ref "D12") (pin "A") (pinfunction "A_A") (pintype "passive"))
      (node (ref "R8") (pin "1") (pinfunction "1_1") (pintype "passive"))
      (node (ref "U3") (pin "27") (pinfunction "IO16_27") (pintype "bidirectional"))
    )
    (net (code "75") (name "TX_SIM") (class "Default")
      (node (ref "SIM800L1") (pin "TXD") (pinfunction "TXD_TXD") (pintype "bidirectional"))
      (node (ref "U3") (pin "23") (pinfunction "IO15_23") (pintype "bidirectional"))
    )
    (net (code "76") (name "USB_N") (class "Default")
      (node (ref "J2") (pin "2") (pinfunction "D-_2") (pintype "passive"))
      (node (ref "U19") (pin "6") (pinfunction "UD-_6") (pintype "bidirectional"))
    )
    (net (code "77") (name "USB_P") (class "Default")
      (node (ref "J2") (pin "3") (pinfunction "D+_3") (pintype "passive"))
      (node (ref "U19") (pin "5") (pinfunction "UD+_5") (pintype "bidirectional"))
    )
    (net (code "78") (name "VCC") (class "Default")
      (node (ref "C11") (pin "2") (pinfunction "2_2") (pintype "passive"))
      (node (ref "D1") (pin "C") (pinfunction "K_C") (pintype "passive"))
      (node (ref "D2") (pin "C") (pinfunction "K_C") (pintype "passive"))
      (node (ref "D3") (pin "C") (pinfunction "K_C") (pintype "passive"))
      (node (ref "D6") (pin "C") (pinfunction "K_C") (pintype "passive"))
      (node (ref "D8") (pin "C") (pinfunction "K_C") (pintype "passive"))
      (node (ref "K1") (pin "A1") (pinfunction "A1_A1") (pintype "passive"))
      (node (ref "K2") (pin "A1") (pinfunction "A1_A1") (pintype "passive"))
      (node (ref "K3") (pin "A1") (pinfunction "A1_A1") (pintype "passive"))
      (node (ref "MINI1") (pin "IN+") (pinfunction "IN+_IN+") (pintype "bidirectional"))
      (node (ref "PZEM004T1") (pin "5V") (pinfunction "5V_5V") (pintype "bidirectional"))
      (node (ref "PZEM004T2") (pin "5V") (pinfunction "5V_5V") (pintype "bidirectional"))
      (node (ref "PZEM004T3") (pin "5V") (pinfunction "5V_5V") (pintype "bidirectional"))
      (node (ref "R2") (pin "2") (pinfunction "2_2") (pintype "passive"))
      (node (ref "R47") (pin "2") (pinfunction "2_2") (pintype "passive"))
      (node (ref "R5") (pin "2") (pinfunction "2_2") (pintype "passive"))
      (node (ref "R7") (pin "2") (pinfunction "2_2") (pintype "passive"))
      (node (ref "R8") (pin "2") (pinfunction "2_2") (pintype "passive"))
      (node (ref "U1") (pin "3") (pinfunction "VIN_3") (pintype "input"))
    )
    (net (code "79") (name "VCC_USB") (class "Default")
      (node (ref "C7") (pin "2") (pinfunction "2_2") (pintype "passive"))
      (node (ref "C8") (pin "+") (pinfunction "+_+") (pintype "passive"))
      (node (ref "D2") (pin "A") (pinfunction "A_A") (pintype "passive"))
      (node (ref "J2") (pin "1") (pinfunction "VUSB_1") (pintype "passive"))
      (node (ref "U19") (pin "16") (pinfunction "VCC_16") (pintype "power_in"))
    )
    (net (code "80") (name "unconnected-(J2-ID-Pad4)") (class "Default")
      (node (ref "J2") (pin "4") (pinfunction "ID_4") (pintype "passive"))
    )
    (net (code "81") (name "unconnected-(K1-PadNC)") (class "Default")
      (node (ref "K1") (pin "NC") (pinfunction "NC_NC") (pintype "passive"))
    )
    (net (code "82") (name "unconnected-(K2-PadNC)") (class "Default")
      (node (ref "K2") (pin "NC") (pinfunction "NC_NC") (pintype "passive"))
    )
    (net (code "83") (name "unconnected-(K3-PadNC)") (class "Default")
      (node (ref "K3") (pin "NC") (pinfunction "NC_NC") (pintype "passive"))
    )
    (net (code "84") (name "unconnected-(LORA-NICERF-V1-PadDIO2)") (class "Default")
      (node (ref "LORA-NICERF-V1") (pin "DIO2") (pinfunction "DIO2_DIO2") (pintype "bidirectional"))
    )
    (net (code "85") (name "unconnected-(LORA-NICERF-V1-PadNC)") (class "Default")
      (node (ref "LORA-NICERF-V1") (pin "NC") (pinfunction "NC_NC") (pintype "bidirectional"))
    )
    (net (code "86") (name "unconnected-(LORA-NICERF-V1-PadNC1)") (class "Default")
      (node (ref "LORA-NICERF-V1") (pin "NC1") (pinfunction "NC1_NC1") (pintype "bidirectional"))
    )
    (net (code "87") (name "unconnected-(RTC1-Pad32K)") (class "Default")
      (node (ref "RTC1") (pin "32K") (pinfunction "32K_32K") (pintype "bidirectional"))
    )
    (net (code "88") (name "unconnected-(RTC1-PadGND1)") (class "Default")
      (node (ref "RTC1") (pin "GND1") (pinfunction "GND1_GND1") (pintype "bidirectional"))
    )
    (net (code "89") (name "unconnected-(RTC1-PadSCL1)") (class "Default")
      (node (ref "RTC1") (pin "SCL1") (pinfunction "SCL1_SCL1") (pintype "bidirectional"))
    )
    (net (code "90") (name "unconnected-(RTC1-PadSDA1)") (class "Default")
      (node (ref "RTC1") (pin "SDA1") (pinfunction "SDA1_SDA1") (pintype "bidirectional"))
    )
    (net (code "91") (name "unconnected-(RTC1-PadSQW)") (class "Default")
      (node (ref "RTC1") (pin "SQW") (pinfunction "SQW_SQW") (pintype "bidirectional"))
    )
    (net (code "92") (name "unconnected-(RTC1-PadVCC1)") (class "Default")
      (node (ref "RTC1") (pin "VCC1") (pinfunction "VCC1_VCC1") (pintype "bidirectional"))
    )
    (net (code "93") (name "unconnected-(SIM800L1-PadDTR)") (class "Default")
      (node (ref "SIM800L1") (pin "DTR") (pinfunction "DTR_DTR") (pintype "bidirectional"))
    )
    (net (code "94") (name "unconnected-(SIM800L1-PadMIC+)") (class "Default")
      (node (ref "SIM800L1") (pin "MIC+") (pinfunction "MIC+_MIC+") (pintype "bidirectional"))
    )
    (net (code "95") (name "unconnected-(SIM800L1-PadMIC-)") (class "Default")
      (node (ref "SIM800L1") (pin "MIC-") (pinfunction "MIC-_MIC-") (pintype "bidirectional"))
    )
    (net (code "96") (name "unconnected-(SIM800L1-PadNET)") (class "Default")
      (node (ref "SIM800L1") (pin "NET") (pinfunction "NET_NET") (pintype "bidirectional"))
    )
    (net (code "97") (name "unconnected-(SIM800L1-PadRING)") (class "Default")
      (node (ref "SIM800L1") (pin "RING") (pinfunction "RING_RING") (pintype "bidirectional"))
    )
    (net (code "98") (name "unconnected-(SIM800L1-PadRST)") (class "Default")
      (node (ref "SIM800L1") (pin "RST") (pinfunction "RST_RST") (pintype "bidirectional"))
    )
    (net (code "99") (name "unconnected-(SIM800L1-PadSPK+)") (class "Default")
      (node (ref "SIM800L1") (pin "SPK+") (pinfunction "SPK+_SPK+") (pintype "bidirectional"))
    )
    (net (code "100") (name "unconnected-(SIM800L1-PadSPK-)") (class "Default")
      (node (ref "SIM800L1") (pin "SPK-") (pinfunction "SPK-_SPK-") (pintype "bidirectional"))
    )
    (net (code "101") (name "unconnected-(U3-IO2-Pad24)") (class "Default")
      (node (ref "U3") (pin "24") (pinfunction "IO2_24") (pintype "bidirectional"))
    )
    (net (code "102") (name "unconnected-(U3-IO4-Pad26)") (class "Default")
      (node (ref "U3") (pin "26") (pinfunction "IO4_26") (pintype "bidirectional"))
    )
    (net (code "103") (name "unconnected-(U3-IO34-Pad6)") (class "Default")
      (node (ref "U3") (pin "6") (pinfunction "IO34_6") (pintype "input"))
    )
    (net (code "104") (name "unconnected-(U3-IO35-Pad7)") (class "Default")
      (node (ref "U3") (pin "7") (pinfunction "IO35_7") (pintype "input"))
    )
    (net (code "105") (name "unconnected-(U3-SCK{slash}CLK-Pad20)") (class "Default")
      (node (ref "U3") (pin "20") (pinfunction "SCK/CLK_20") (pintype "bidirectional"))
    )
    (net (code "106") (name "unconnected-(U3-SCS{slash}CMD-Pad19)") (class "Default")
      (node (ref "U3") (pin "19") (pinfunction "SCS/CMD_19") (pintype "bidirectional"))
    )
    (net (code "107") (name "unconnected-(U3-SDI{slash}SD1-Pad22)") (class "Default")
      (node (ref "U3") (pin "22") (pinfunction "SDI/SD1_22") (pintype "bidirectional"))
    )
    (net (code "108") (name "unconnected-(U3-SDO{slash}SD0-Pad21)") (class "Default")
      (node (ref "U3") (pin "21") (pinfunction "SDO/SD0_21") (pintype "bidirectional"))
    )
    (net (code "109") (name "unconnected-(U3-SENSOR_VN-Pad5)") (class "Default")
      (node (ref "U3") (pin "5") (pinfunction "SENSOR_VN_5") (pintype "input"))
    )
    (net (code "110") (name "unconnected-(U3-SENSOR_VP-Pad4)") (class "Default")
      (node (ref "U3") (pin "4") (pinfunction "SENSOR_VP_4") (pintype "input"))
    )
    (net (code "111") (name "unconnected-(U3-SHD{slash}SD2-Pad17)") (class "Default")
      (node (ref "U3") (pin "17") (pinfunction "SHD/SD2_17") (pintype "bidirectional"))
    )
    (net (code "112") (name "unconnected-(U3-SWP{slash}SD3-Pad18)") (class "Default")
      (node (ref "U3") (pin "18") (pinfunction "SWP/SD3_18") (pintype "bidirectional"))
    )
    (net (code "113") (name "unconnected-(U19-RS232-Pad15)") (class "Default")
      (node (ref "U19") (pin "15") (pinfunction "RS232_15") (pintype "input"))
    )
    (net (code "114") (name "unconnected-(U19-~{CTS}-Pad9)") (class "Default")
      (node (ref "U19") (pin "9") (pinfunction "~{CTS}_9") (pintype "input"))
    )
    (net (code "115") (name "unconnected-(U19-~{DCD}-Pad12)") (class "Default")
      (node (ref "U19") (pin "12") (pinfunction "~{DCD}_12") (pintype "input"))
    )
    (net (code "116") (name "unconnected-(U19-~{DSR}-Pad10)") (class "Default")
      (node (ref "U19") (pin "10") (pinfunction "~{DSR}_10") (pintype "input"))
    )
    (net (code "117") (name "unconnected-(U19-~{RI}-Pad11)") (class "Default")
      (node (ref "U19") (pin "11") (pinfunction "~{RI}_11") (pintype "input"))
    )
  )
)
